# PCB_Project_Board_3.net
KiCad netlist of a schematic drawn in Altium Designer
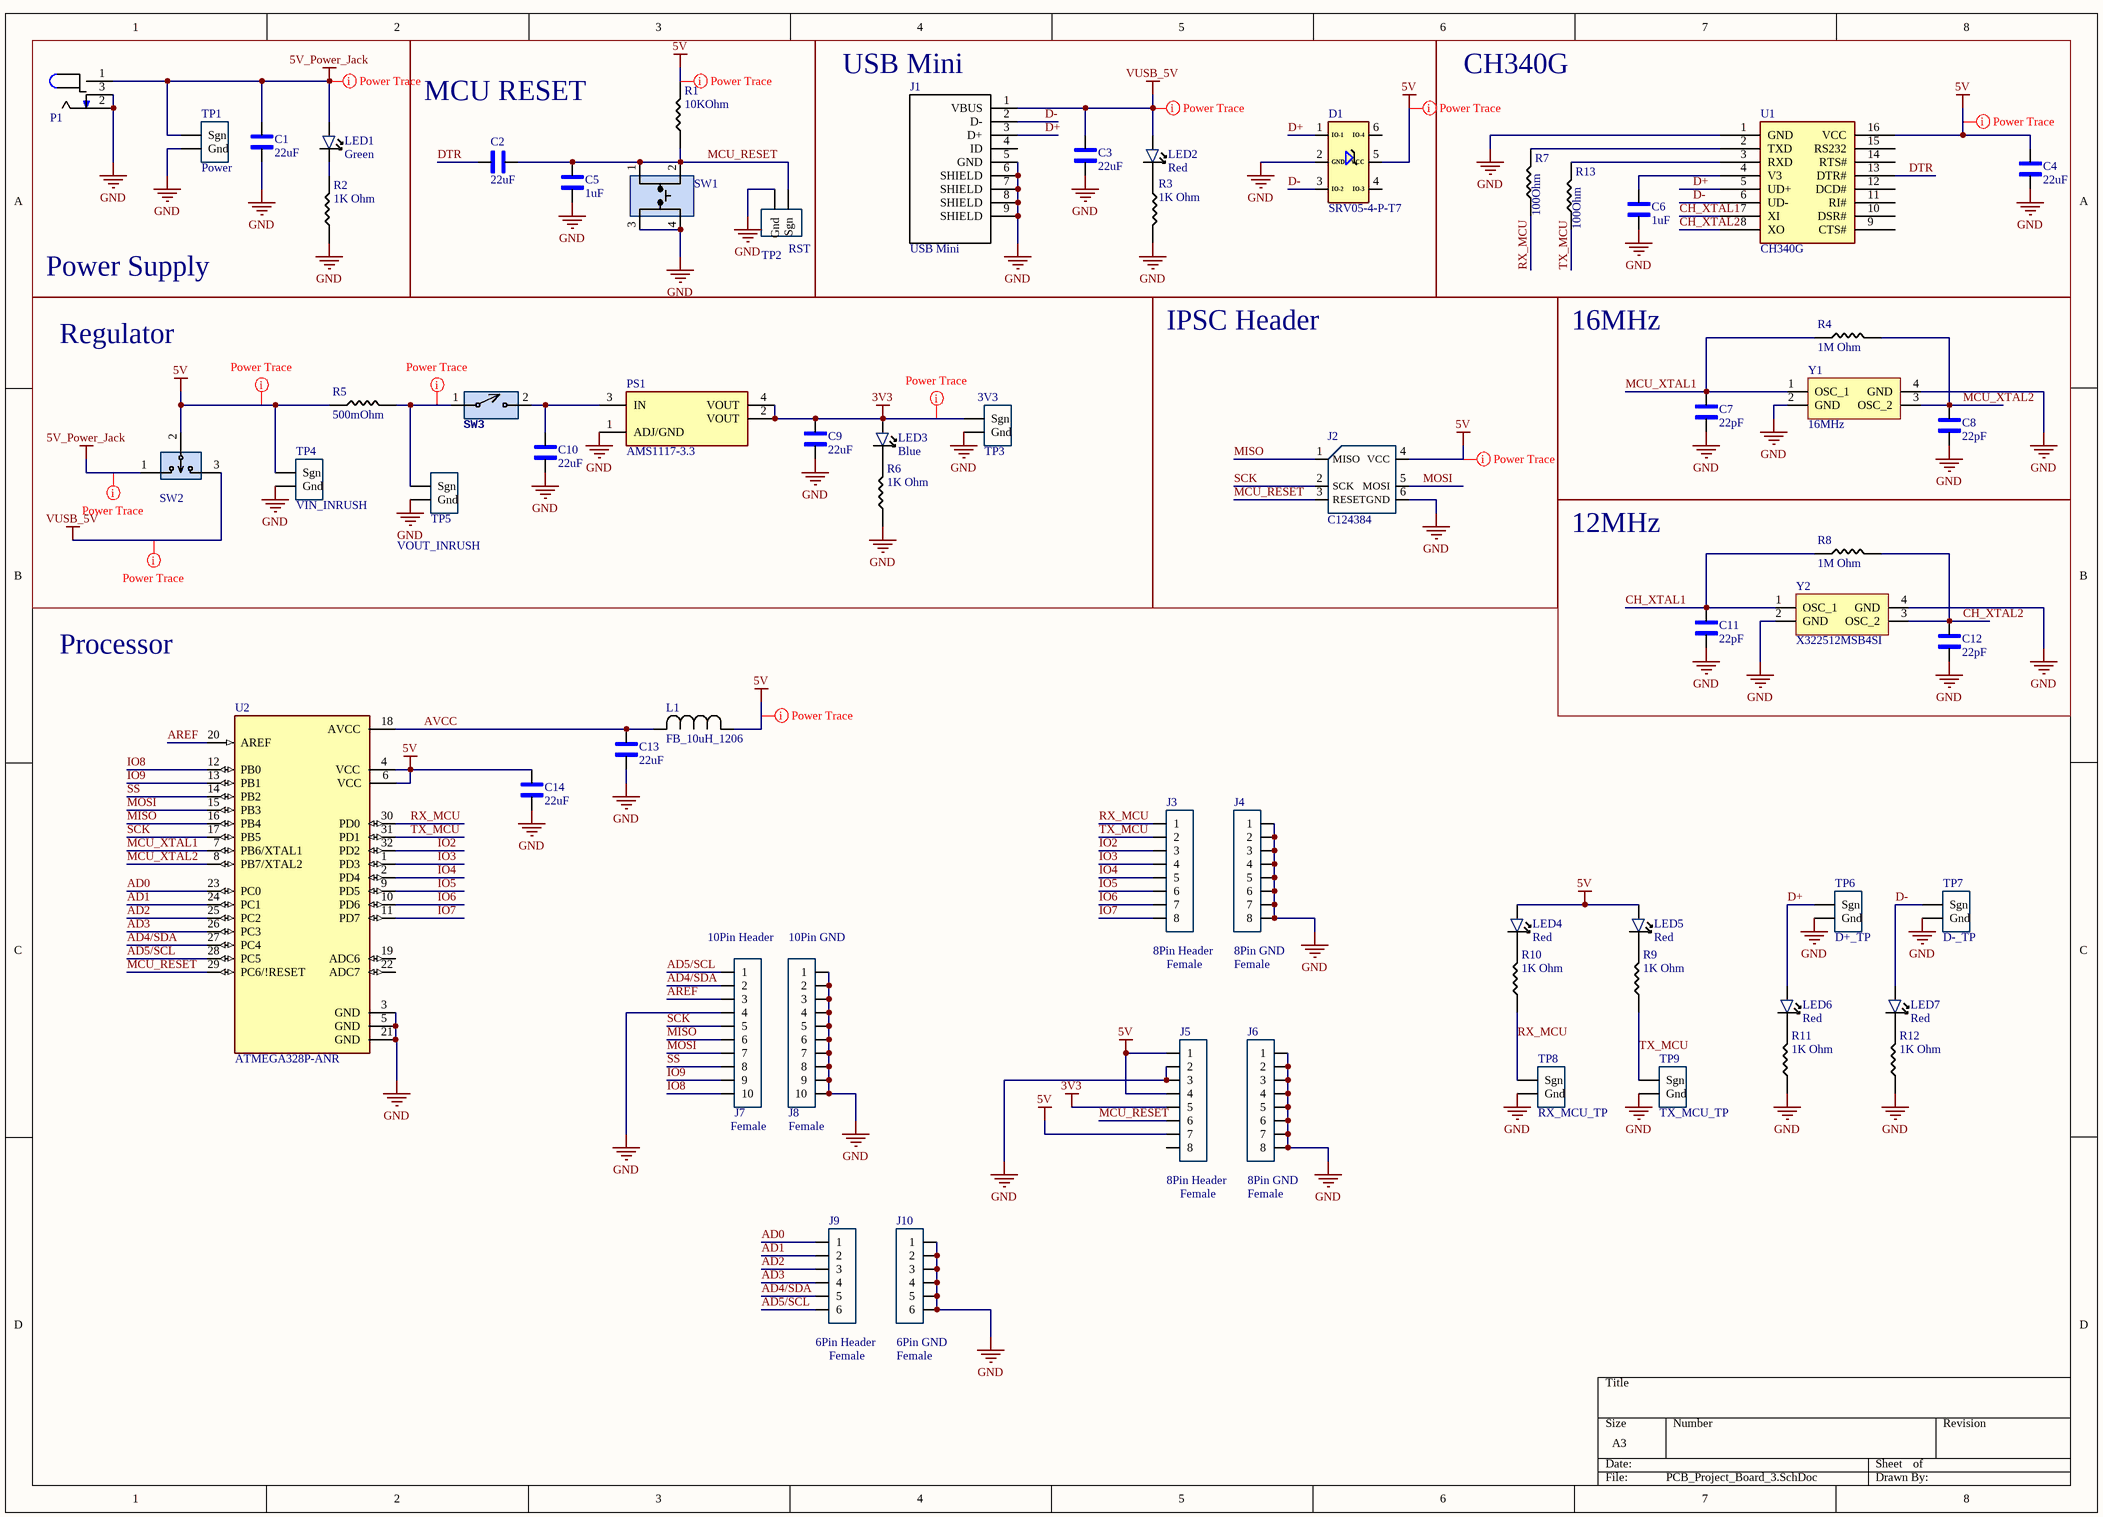
[diagram p0: PCB_Project_Board_3.SchDoc]

(export (version "E")
  (design (tool "Eeschema 10.0.6"))
  (components
    (comp (ref "C1")
      (value "22uF")
      (footprint "1206_Passive_Capacitor")
      (description "22uF ±10% 25V X5R 1206 Multilayer Ceramic Capacitors MLCC - SMD/SMT RoHS")
      (fields (field (name "MFR PART #") "CL31A226KAHNNNE") (field (name "LCSC PART#") "C12891"))
      (libsource (lib "ECEN5730Lib_2023_01_DS") (part "C_22uF_1206"))
    )
    (comp (ref "C2")
      (value "22uF")
      (footprint "1206_Passive_Capacitor")
      (description "22uF ±10% 25V X5R 1206 Multilayer Ceramic Capacitors MLCC - SMD/SMT RoHS")
      (fields (field (name "MFR PART #") "CL31A226KAHNNNE") (field (name "LCSC PART#") "C12891"))
      (libsource (lib "ECEN5730Lib_2023_01_DS") (part "C_22uF_1206"))
    )
    (comp (ref "C3")
      (value "22uF")
      (footprint "1206_Passive_Capacitor")
      (description "22uF ±10% 25V X5R 1206 Multilayer Ceramic Capacitors MLCC - SMD/SMT RoHS")
      (fields (field (name "MFR PART #") "CL31A226KAHNNNE") (field (name "LCSC PART#") "C12891"))
      (libsource (lib "ECEN5730Lib_2023_01_DS") (part "C_22uF_1206"))
    )
    (comp (ref "C4")
      (value "22uF")
      (footprint "1206_Passive_Capacitor")
      (description "22uF ±10% 25V X5R 1206 Multilayer Ceramic Capacitors MLCC - SMD/SMT RoHS")
      (fields (field (name "MFR PART #") "CL31A226KAHNNNE") (field (name "LCSC PART#") "C12891"))
      (libsource (lib "ECEN5730Lib_2023_01_DS") (part "C_22uF_1206"))
    )
    (comp (ref "C5")
      (value "1uF")
      (footprint "1206_Passive_Capacitor")
      (description "MULTILAYER CERAMIC CAPACITORS MLCC - SMD/SMT 1UF 50V 1206 ROHS")
      (fields (field (name "MFR PART #") "CL31B105KBHNNNE") (field (name "LCSC PART#") "C1848"))
      (libsource (lib "ECEN5730Lib_2023_01_DS") (part "C_1uF_1206"))
    )
    (comp (ref "C6")
      (value "1uF")
      (footprint "1206_Passive_Capacitor")
      (description "MULTILAYER CERAMIC CAPACITORS MLCC - SMD/SMT 1UF 50V 1206 ROHS")
      (fields (field (name "MFR PART #") "CL31B105KBHNNNE") (field (name "LCSC PART#") "C1848"))
      (libsource (lib "ECEN5730Lib_2023_01_DS") (part "C_1uF_1206"))
    )
    (comp (ref "C7")
      (value "22pF")
      (footprint "1206_Passive_Capacitor")
      (description "22pF ±5% 1kV C0G 1206 Multilayer Ceramic Capacitors MLCC - SMD/SMT RoHS")
      (fields (field (name "LCSC PART#") "C313096") (field (name "MFR PART #") "1206CG220J102NT"))
      (libsource (lib "ECEN5730Lib_2023_01_DS") (part "C_22pF_1206"))
    )
    (comp (ref "C8")
      (value "22pF")
      (footprint "1206_Passive_Capacitor")
      (description "22pF ±5% 1kV C0G 1206 Multilayer Ceramic Capacitors MLCC - SMD/SMT RoHS")
      (fields (field (name "LCSC PART#") "C313096") (field (name "MFR PART #") "1206CG220J102NT"))
      (libsource (lib "ECEN5730Lib_2023_01_DS") (part "C_22pF_1206"))
    )
    (comp (ref "C9")
      (value "22uF")
      (footprint "1206_Passive_Capacitor")
      (description "22uF ±10% 25V X5R 1206 Multilayer Ceramic Capacitors MLCC - SMD/SMT RoHS")
      (fields (field (name "MFR PART #") "CL31A226KAHNNNE") (field (name "LCSC PART#") "C12891"))
      (libsource (lib "ECEN5730Lib_2023_01_DS") (part "C_22uF_1206"))
    )
    (comp (ref "C10")
      (value "22uF")
      (footprint "1206_Passive_Capacitor")
      (description "22uF ±10% 25V X5R 1206 Multilayer Ceramic Capacitors MLCC - SMD/SMT RoHS")
      (fields (field (name "MFR PART #") "CL31A226KAHNNNE") (field (name "LCSC PART#") "C12891"))
      (libsource (lib "ECEN5730Lib_2023_01_DS") (part "C_22uF_1206"))
    )
    (comp (ref "C11")
      (value "22pF")
      (footprint "1206_Passive_Capacitor")
      (description "22pF ±5% 1kV C0G 1206 Multilayer Ceramic Capacitors MLCC - SMD/SMT RoHS")
      (fields (field (name "LCSC PART#") "C313096") (field (name "MFR PART #") "1206CG220J102NT"))
      (libsource (lib "ECEN5730Lib_2023_01_DS") (part "C_22pF_1206"))
    )
    (comp (ref "C12")
      (value "22pF")
      (footprint "1206_Passive_Capacitor")
      (description "22pF ±5% 1kV C0G 1206 Multilayer Ceramic Capacitors MLCC - SMD/SMT RoHS")
      (fields (field (name "LCSC PART#") "C313096") (field (name "MFR PART #") "1206CG220J102NT"))
      (libsource (lib "ECEN5730Lib_2023_01_DS") (part "C_22pF_1206"))
    )
    (comp (ref "C13")
      (value "22uF")
      (footprint "1206_Passive_Capacitor")
      (description "22uF ±10% 25V X5R 1206 Multilayer Ceramic Capacitors MLCC - SMD/SMT RoHS")
      (fields (field (name "MFR PART #") "CL31A226KAHNNNE") (field (name "LCSC PART#") "C12891"))
      (libsource (lib "ECEN5730Lib_2023_01_DS") (part "C_22uF_1206"))
    )
    (comp (ref "C14")
      (value "22uF")
      (footprint "1206_Passive_Capacitor")
      (description "22uF ±10% 25V X5R 1206 Multilayer Ceramic Capacitors MLCC - SMD/SMT RoHS")
      (fields (field (name "MFR PART #") "CL31A226KAHNNNE") (field (name "LCSC PART#") "C12891"))
      (libsource (lib "ECEN5730Lib_2023_01_DS") (part "C_22uF_1206"))
    )
    (comp (ref "D1")
      (value "SRV05-4-P-T7")
      (footprint "TVS")
      (description "TVS SOT-23-6 ROHS")
      (fields (field (name "LCSC PART#") "C85364"))
      (libsource (lib "ECEN5730Lib_2023_01_DS") (part "D_TVS_Diode"))
    )
    (comp (ref "J1")
      (value "USB Mini")
      (footprint "USB_MINI_B")
      (description "Through Hole USB Connectors RoHS")
      (fields (field (name "LCSC PART#") "C46398") (field (name "MFR PART #") "920-462A2021D10102"))
      (libsource (lib "ECEN5730Lib_2023_01_DS") (part "J_USB_B_Mini"))
    )
    (comp (ref "J2")
      (value "NRPN032PAEN-RC")
      (footprint "ICSP")
      (description "Connector Header Through Hole 6 position 0.079\" (2.00mm)")
      (fields (field (name "LCSC PART#") "C124384"))
      (libsource (lib "ECEN5730Lib_2023_01_DS") (part "J_ICSP"))
    )
    (comp (ref "J3")
      (value "8Pin Header")
      (footprint "8_PIN_100MIL - Female")
      (description "8 Position Header Connector 0.100\" (2.54mm) Through Hole Tin")
      (fields
        (field (name "MFR PART #") "PPTC081LFBN-RC")
        (field (name "LCSC PART#") "C27438")
        (field (name "ALTIUM_VALUE") "Female")
      )
      (libsource (lib "ECEN5730Lib_2023_01_DS") (part "JF_8_PIN_FEMALE"))
    )
    (comp (ref "J4")
      (value "8Pin GND")
      (footprint "8_PIN_100MIL - Female")
      (description "8 Position Header Connector 0.100\" (2.54mm) Through Hole Tin")
      (fields
        (field (name "MFR PART #") "PPTC081LFBN-RC")
        (field (name "LCSC PART#") "C27438")
        (field (name "ALTIUM_VALUE") "Female")
      )
      (libsource (lib "") (part "JF_8_PIN_FEMALE_1"))
    )
    (comp (ref "J5")
      (value "8Pin Header")
      (footprint "8_PIN_100MIL - Female")
      (description "8 Position Header Connector 0.100\" (2.54mm) Through Hole Tin")
      (fields
        (field (name "MFR PART #") "PPTC081LFBN-RC")
        (field (name "LCSC PART#") "C27438")
        (field (name "ALTIUM_VALUE") "Female")
      )
      (libsource (lib "ECEN5730Lib_2023_01_DS") (part "JF_8_PIN_FEMALE"))
    )
    (comp (ref "J6")
      (value "8Pin GND")
      (footprint "8_PIN_100MIL - Female")
      (description "8 Position Header Connector 0.100\" (2.54mm) Through Hole Tin")
      (fields
        (field (name "MFR PART #") "PPTC081LFBN-RC")
        (field (name "LCSC PART#") "C27438")
        (field (name "ALTIUM_VALUE") "Female")
      )
      (libsource (lib "") (part "JF_8_PIN_FEMALE_1"))
    )
    (comp (ref "J7")
      (value "10Pin Header")
      (footprint "10_PIN_100MIL - Female")
      (description "10 Position Header Connector 0.100\" (2.54mm) Through Hole Tin")
      (fields
        (field (name "MFR PART #") "PPTC101LFBN-RC")
        (field (name "LCSC PART#") "C225507")
        (field (name "ALTIUM_VALUE") "Female")
      )
      (libsource (lib "") (part "JF_10_PIN_FEMALE__1"))
    )
    (comp (ref "J8")
      (value "10Pin GND")
      (footprint "10_PIN_100MIL - Female")
      (description "10 Position Header Connector 0.100\" (2.54mm) Through Hole Tin")
      (fields
        (field (name "MFR PART #") "PPTC101LFBN-RC")
        (field (name "LCSC PART#") "C225507")
        (field (name "ALTIUM_VALUE") "Female")
      )
      (libsource (lib "ECEN5730Lib_2023_01_DS") (part "JF_10_PIN_FEMALE_"))
    )
    (comp (ref "J9")
      (value "6Pin Header")
      (footprint "6_PIN_100MIL -Female")
      (description "6 Position Header Connector 0.100\" (2.54mm) Through Hole Tin")
      (fields
        (field (name "MFR PART #") "PPTC061LFBN-RC")
        (field (name "LCSC PART#") "C40877")
        (field (name "ALTIUM_VALUE") "Female")
      )
      (libsource (lib "ECEN5730Lib_2023_01_DS") (part "JF_6_PIN_FEMALE"))
    )
    (comp (ref "J10")
      (value "6Pin GND")
      (footprint "6_PIN_100MIL -Female")
      (description "6 Position Header Connector 0.100\" (2.54mm) Through Hole Tin")
      (fields
        (field (name "MFR PART #") "PPTC061LFBN-RC")
        (field (name "LCSC PART#") "C40877")
        (field (name "ALTIUM_VALUE") "Female")
      )
      (libsource (lib "") (part "JF_6_PIN_FEMALE_1"))
    )
    (comp (ref "L1")
      (value "FB_10uH_1206")
      (footprint "AIML-1206_ABR-M")
      (description "25mA 10uH ±10% 800mΩ 1206  Inductors (SMD) ROHS")
      (fields (field (name "MFR PART #") "CMI321609X100KT") (field (name "LCSC PART#") "C1051"))
      (libsource (lib "ECEN5730Lib_2023_01_DS") (part "FB_10uH_1206"))
    )
    (comp (ref "LED1")
      (value "Green")
      (footprint "LED_1206")
      (description "Green 513~528nm 1206 Light Emitting Diodes (LED) RoHS")
      (fields (field (name "MFR PART #") "SZYY1206G") (field (name "LCSC PART#") "C434439"))
      (libsource (lib "ECEN5730Lib_2023_01_DS") (part "LED_GREEN_1206"))
    )
    (comp (ref "LED2")
      (value "Red")
      (footprint "LED_1206")
      (description "Red 621~631nm 1206 Light Emitting Diodes (LED) RoHS")
      (fields (field (name "MFR PART #") "15-21/R6C-FQ1R1B/2T") (field (name "LCSC PART#") "C93133"))
      (libsource (lib "ECEN5730Lib_2023_01_DS") (part "LED_RED_1206"))
    )
    (comp (ref "LED3")
      (value "Blue")
      (footprint "LED_1206")
      (description "blue 1206  Light Emitting Diodes (LED) ROHS")
      (fields (field (name "MFR PART #") "NCD1206B1") (field (name "LCSC PART#") "C130717"))
      (libsource (lib "ECEN5730Lib_2023_01_DS") (part "LED_BLUE_1206"))
    )
    (comp (ref "LED4")
      (value "Red")
      (footprint "LED_1206")
      (description "Red 621~631nm 1206 Light Emitting Diodes (LED) RoHS")
      (fields (field (name "MFR PART #") "15-21/R6C-FQ1R1B/2T") (field (name "LCSC PART#") "C93133"))
      (libsource (lib "ECEN5730Lib_2023_01_DS") (part "LED_RED_1206"))
    )
    (comp (ref "LED5")
      (value "Red")
      (footprint "LED_1206")
      (description "Red 621~631nm 1206 Light Emitting Diodes (LED) RoHS")
      (fields (field (name "MFR PART #") "15-21/R6C-FQ1R1B/2T") (field (name "LCSC PART#") "C93133"))
      (libsource (lib "ECEN5730Lib_2023_01_DS") (part "LED_RED_1206"))
    )
    (comp (ref "LED6")
      (value "Red")
      (footprint "LED_1206")
      (description "Red 621~631nm 1206 Light Emitting Diodes (LED) RoHS")
      (fields (field (name "MFR PART #") "15-21/R6C-FQ1R1B/2T") (field (name "LCSC PART#") "C93133"))
      (libsource (lib "ECEN5730Lib_2023_01_DS") (part "LED_RED_1206"))
    )
    (comp (ref "LED7")
      (value "Red")
      (footprint "LED_1206")
      (description "Red 621~631nm 1206 Light Emitting Diodes (LED) RoHS")
      (fields (field (name "MFR PART #") "15-21/R6C-FQ1R1B/2T") (field (name "LCSC PART#") "C93133"))
      (libsource (lib "ECEN5730Lib_2023_01_DS") (part "LED_RED_1206"))
    )
    (comp (ref "P1")
      (value "Power Jack")
      (footprint "Power_Jack")
      (description "Power Barrel Connector Jack 2.10mm ID (0.083\"), 5.50mm OD (0.217\") Through Hole, Right Angle")
      (fields (field (name "MFR PART #") "PJ-102A") (field (name "LCSC PART#") "C136744"))
      (libsource (lib "ECEN5730Lib_2023_01_DS") (part "P_Power Jack"))
    )
    (comp (ref "PS1")
      (value "AMS1117-3.3")
      (footprint "LDO")
      (description "LOW DROPOUT REGULATORS(LDO) POSITIVE FIXED 1.3V @ 800MA 15V 3.3V 1A SOT-223 ROHS")
      (fields (field (name "LCSC PART#") "C6186"))
      (libsource (lib "ECEN5730Lib_2023_01_DS") (part "PS_AMS_LDO_3v3"))
    )
    (comp (ref "R1")
      (value "10KOhm")
      (footprint "1206_Passive_Resitor")
      (description "10 kOhms ±5% 0.25W, 1/4W Chip Resistor 1206 (3216 Metric) Automotive AEC-Q200 Thick Film")
      (fields (field (name "MFR PART #") "RMCF1206FT10K0") (field (name "LCSC PART#") "C17902"))
      (libsource (lib "ECEN5730Lib_2023_01_DS") (part "R_10KOhm_1206"))
    )
    (comp (ref "R2")
      (value "1K Ohm")
      (footprint "1206_Passive_Resitor")
      (description "CHIP RESISTOR - SURFACE MOUNT 1KOHMS ±1% 1/4W 1206 ROHS")
      (fields (field (name "MFR PART #") "RNCP1206FTD1K00CT") (field (name "LCSC PART#") "C4410"))
      (libsource (lib "ECEN5730Lib_2023_01_DS") (part "R_1K_1206"))
    )
    (comp (ref "R3")
      (value "1K Ohm")
      (footprint "1206_Passive_Resitor")
      (description "CHIP RESISTOR - SURFACE MOUNT 1KOHMS ±1% 1/4W 1206 ROHS")
      (fields (field (name "MFR PART #") "RNCP1206FTD1K00CT") (field (name "LCSC PART#") "C4410"))
      (libsource (lib "ECEN5730Lib_2023_01_DS") (part "R_1K_1206"))
    )
    (comp (ref "R4")
      (value "1M Ohm")
      (footprint "1206_Passive_Resitor")
      (description "CHIP RESISTOR - SURFACE MOUNT 1MOHMS ±1% 1/4W 1206 ROHS")
      (fields (field (name "MFR PART #") "RMCF1206JT1M00") (field (name "LCSC PART#") "C17927"))
      (libsource (lib "ECEN5730Lib_2023_01_DS") (part "R_1M_1206"))
    )
    (comp (ref "R5")
      (value "500mOhm")
      (footprint "1206_Passive_Resitor")
      (description "Resistors/Shunt 250mW 500mΩ ±800ppm/℃ ±5% 1206  Current Sense  Resistors ROHS")
      (fields (field (name "MFR PART #") "1206W4J050KT5E") (field (name "LCSC PART#") "C247433"))
      (libsource (lib "ECEN5730Lib_2023_01_DS") (part "R_500mOhm_1206"))
    )
    (comp (ref "R6")
      (value "1K Ohm")
      (footprint "1206_Passive_Resitor")
      (description "CHIP RESISTOR - SURFACE MOUNT 1KOHMS ±1% 1/4W 1206 ROHS")
      (fields (field (name "MFR PART #") "RNCP1206FTD1K00CT") (field (name "LCSC PART#") "C4410"))
      (libsource (lib "ECEN5730Lib_2023_01_DS") (part "R_1K_1206"))
    )
    (comp (ref "R7")
      (value "100Ohm")
      (footprint "1206_Passive_Resitor")
      (description "100Ω ±1% 0.25W ±100ppm/℃ 1206 Chip Resistor - Surface Mount RoHS")
      (fields (field (name "LCSC PART#") "C17901") (field (name "MFR PART #") "1206W4F1000T5E"))
      (libsource (lib "ECEN5730Lib_2023_01_DS") (part "R_100Ohm_1206"))
    )
    (comp (ref "R8")
      (value "1M Ohm")
      (footprint "1206_Passive_Resitor")
      (description "CHIP RESISTOR - SURFACE MOUNT 1MOHMS ±1% 1/4W 1206 ROHS")
      (fields (field (name "MFR PART #") "RMCF1206JT1M00") (field (name "LCSC PART#") "C17927"))
      (libsource (lib "ECEN5730Lib_2023_01_DS") (part "R_1M_1206"))
    )
    (comp (ref "R9")
      (value "1K Ohm")
      (footprint "1206_Passive_Resitor")
      (description "CHIP RESISTOR - SURFACE MOUNT 1KOHMS ±1% 1/4W 1206 ROHS")
      (fields (field (name "MFR PART #") "RNCP1206FTD1K00CT") (field (name "LCSC PART#") "C4410"))
      (libsource (lib "ECEN5730Lib_2023_01_DS") (part "R_1K_1206"))
    )
    (comp (ref "R10")
      (value "1K Ohm")
      (footprint "1206_Passive_Resitor")
      (description "CHIP RESISTOR - SURFACE MOUNT 1KOHMS ±1% 1/4W 1206 ROHS")
      (fields (field (name "MFR PART #") "RNCP1206FTD1K00CT") (field (name "LCSC PART#") "C4410"))
      (libsource (lib "ECEN5730Lib_2023_01_DS") (part "R_1K_1206"))
    )
    (comp (ref "R11")
      (value "1K Ohm")
      (footprint "1206_Passive_Resitor")
      (description "CHIP RESISTOR - SURFACE MOUNT 1KOHMS ±1% 1/4W 1206 ROHS")
      (fields (field (name "MFR PART #") "RNCP1206FTD1K00CT") (field (name "LCSC PART#") "C4410"))
      (libsource (lib "ECEN5730Lib_2023_01_DS") (part "R_1K_1206"))
    )
    (comp (ref "R12")
      (value "1K Ohm")
      (footprint "1206_Passive_Resitor")
      (description "CHIP RESISTOR - SURFACE MOUNT 1KOHMS ±1% 1/4W 1206 ROHS")
      (fields (field (name "MFR PART #") "RNCP1206FTD1K00CT") (field (name "LCSC PART#") "C4410"))
      (libsource (lib "ECEN5730Lib_2023_01_DS") (part "R_1K_1206"))
    )
    (comp (ref "R13")
      (value "100Ohm")
      (footprint "1206_Passive_Resitor")
      (description "100Ω ±1% 0.25W ±100ppm/℃ 1206 Chip Resistor - Surface Mount RoHS")
      (fields (field (name "LCSC PART#") "C17901") (field (name "MFR PART #") "1206W4F1000T5E"))
      (libsource (lib "ECEN5730Lib_2023_01_DS") (part "R_100Ohm_1206"))
    )
    (comp (ref "SW1")
      (value "TL3305AF160QG")
      (footprint "Switch_JLC")
      (description "Tactile Switch SPST-NO Top Actuated Surface Mount")
      (fields (field (name "MFR PART #") "KH-4.5X4.5X4.3H-STM") (field (name "LCSC PART#") "C2837550"))
      (libsource (lib "ECEN5730Lib_2023_01_DS") (part "SW_Push_Button_JLC"))
    )
    (comp (ref "SW2")
      (value "PREC003SAAN-RC")
      (footprint "3_PIN_100mil")
      (description "Connector Header Through Hole 3 position 0.100\" (2.54mm)")
      (fields (field (name "LCSC PART#") "C49257"))
      (libsource (lib "ECEN5730Lib_2023_01_DS") (part "SW_3Pin_100mil_Switch"))
    )
    (comp (ref "SW3")
      (value "SW_2Pin_100mil_Switch")
      (footprint "2Pin-Header-Conn")
      (description "2Pin Header")
      (fields (field (name "LCSC PART#") "C124375"))
      (libsource (lib "ECEN5730Lib_2023_01_DS") (part "SW_2Pin_100mil_Switch"))
    )
    (comp (ref "TP1")
      (value "Power")
      (footprint "TP10x_Probe")
      (description "Test Point 300 mil centers")
      (libsource (lib "ECEN5730Lib_2023_01_DS") (part "TP_10x_Probe"))
    )
    (comp (ref "TP2")
      (value "RST")
      (footprint "TP10x_Probe")
      (description "Test Point 300 mil centers")
      (libsource (lib "") (part "TP_10x_Probe_1"))
    )
    (comp (ref "TP3")
      (value "3V3")
      (footprint "TP10x_Probe")
      (description "Test Point 300 mil centers")
      (libsource (lib "ECEN5730Lib_2023_01_DS") (part "TP_10x_Probe"))
    )
    (comp (ref "TP4")
      (value "VIN_INRUSH")
      (footprint "TP10x_Probe")
      (description "Test Point 300 mil centers")
      (libsource (lib "ECEN5730Lib_2023_01_DS") (part "TP_10x_Probe"))
    )
    (comp (ref "TP5")
      (value "VOUT_INRUSH")
      (footprint "TP10x_Probe")
      (description "Test Point 300 mil centers")
      (libsource (lib "ECEN5730Lib_2023_01_DS") (part "TP_10x_Probe"))
    )
    (comp (ref "TP6")
      (value "D+_TP")
      (footprint "TP10x_Probe")
      (description "Test Point 300 mil centers")
      (libsource (lib "ECEN5730Lib_2023_01_DS") (part "TP_10x_Probe"))
    )
    (comp (ref "TP7")
      (value "D-_TP")
      (footprint "TP10x_Probe")
      (description "Test Point 300 mil centers")
      (libsource (lib "ECEN5730Lib_2023_01_DS") (part "TP_10x_Probe"))
    )
    (comp (ref "TP8")
      (value "RX_MCU_TP")
      (footprint "TP10x_Probe")
      (description "Test Point 300 mil centers")
      (libsource (lib "ECEN5730Lib_2023_01_DS") (part "TP_10x_Probe"))
    )
    (comp (ref "TP9")
      (value "TX_MCU_TP")
      (footprint "TP10x_Probe")
      (description "Test Point 300 mil centers")
      (libsource (lib "ECEN5730Lib_2023_01_DS") (part "TP_10x_Probe"))
    )
    (comp (ref "U1")
      (value "CH340G")
      (footprint "USB to serial")
      (description "Transceiver USB 2.0 2Mbps SOP-16_150mil USB ICs RoHS")
      (fields (field (name "LCSC PART#") "C14267"))
      (libsource (lib "ECEN5730Lib_2023_01_DS") (part "U_USBtoSerial"))
    )
    (comp (ref "U2")
      (value "ATMEGA328P-ANR")
      (footprint "ATMega328P")
      (description "AVR AVR® ATmega Microcontroller IC 8-Bit 20MHz 32KB (16K x 16) FLASH 32-TQFP (7x7)")
      (fields (field (name "MFR PART #") "ATMEGA328P-AU") (field (name "LCSC PART#") "C14877"))
      (libsource (lib "ECEN5730Lib_2023_01_DS") (part "U_ATMega328P"))
    )
    (comp (ref "Y1")
      (value "16MHz")
      (footprint "Crystal resonator")
      (description "±10ppm 16000000Hz -40℃~85℃ 贴片无源晶振 60Ω 9pF SMD3225-4P Crystals ROHS")
      (fields (field (name "LCSC PART#") "C13738") (field (name "MFR PART #") "X322516MLB4SI"))
      (libsource (lib "ECEN5730Lib_2023_01_DS") (part "X_16Mhz_Res"))
    )
    (comp (ref "Y2")
      (value "X322512MSB4SI")
      (footprint "Crystal resonator")
      (description "SMD Crystal Resonators 12MHz ±10ppm SMD-3225_4P RoHS")
      (fields (field (name "LCSC PART#") "C9002"))
      (libsource (lib "ECEN5730Lib_2023_01_DS") (part "X_12MHz_Res"))
    )
  )
  (nets
    (net (code "1") (name "/AD0") (class "Default")
      (node (ref "J9") (pin "1") (pinfunction "1_1") (pintype "passive"))
      (node (ref "U2") (pin "23") (pinfunction "PC0_23") (pintype "bidirectional"))
    )
    (net (code "2") (name "/AD1") (class "Default")
      (node (ref "J9") (pin "2") (pinfunction "2_2") (pintype "passive"))
      (node (ref "U2") (pin "24") (pinfunction "PC1_24") (pintype "bidirectional"))
    )
    (net (code "3") (name "/AD2") (class "Default")
      (node (ref "J9") (pin "3") (pinfunction "3_3") (pintype "passive"))
      (node (ref "U2") (pin "25") (pinfunction "PC2_25") (pintype "bidirectional"))
    )
    (net (code "4") (name "/AD3") (class "Default")
      (node (ref "J9") (pin "4") (pinfunction "4_4") (pintype "passive"))
      (node (ref "U2") (pin "26") (pinfunction "PC3_26") (pintype "bidirectional"))
    )
    (net (code "5") (name "/AD4{slash}SDA") (class "Default")
      (node (ref "J7") (pin "2") (pinfunction "2_2") (pintype "passive"))
      (node (ref "J9") (pin "5") (pinfunction "5_5") (pintype "passive"))
      (node (ref "U2") (pin "27") (pinfunction "PC4_27") (pintype "bidirectional"))
    )
    (net (code "6") (name "/AD5{slash}SCL") (class "Default")
      (node (ref "J7") (pin "1") (pinfunction "1_1") (pintype "passive"))
      (node (ref "J9") (pin "6") (pinfunction "6_6") (pintype "passive"))
      (node (ref "U2") (pin "28") (pinfunction "PC5_28") (pintype "bidirectional"))
    )
    (net (code "7") (name "/AREF") (class "Default")
      (node (ref "J7") (pin "3") (pinfunction "3_3") (pintype "passive"))
      (node (ref "U2") (pin "20") (pinfunction "AREF_20") (pintype "input"))
    )
    (net (code "8") (name "/AVCC") (class "Default")
      (node (ref "C13") (pin "2") (pinfunction "2_2") (pintype "passive"))
      (node (ref "L1") (pin "2") (pinfunction "2_2") (pintype "passive"))
      (node (ref "U2") (pin "18") (pinfunction "AVCC_18") (pintype "power_in"))
    )
    (net (code "9") (name "/CH_XTAL1") (class "Default")
      (node (ref "C11") (pin "2") (pinfunction "2_2") (pintype "passive"))
      (node (ref "R8") (pin "1") (pinfunction "1_1") (pintype "passive"))
      (node (ref "U1") (pin "7") (pinfunction "XI_7") (pintype "passive"))
      (node (ref "Y2") (pin "1") (pinfunction "OSC_1_1") (pintype "passive"))
    )
    (net (code "10") (name "/CH_XTAL2") (class "Default")
      (node (ref "C12") (pin "2") (pinfunction "2_2") (pintype "passive"))
      (node (ref "R8") (pin "2") (pinfunction "2_2") (pintype "passive"))
      (node (ref "U1") (pin "8") (pinfunction "XO_8") (pintype "passive"))
      (node (ref "Y2") (pin "3") (pinfunction "OSC_2_3") (pintype "passive"))
    )
    (net (code "11") (name "/D+") (class "Default")
      (node (ref "D1") (pin "1") (pinfunction "IO-1_1") (pintype "passive"))
      (node (ref "J1") (pin "3") (pinfunction "D+_3") (pintype "passive"))
      (node (ref "LED6") (pin "1") (pinfunction "1_1") (pintype "passive"))
      (node (ref "TP6") (pin "1") (pinfunction "Sgn_1") (pintype "passive"))
      (node (ref "U1") (pin "5") (pinfunction "UD+_5") (pintype "passive"))
    )
    (net (code "12") (name "/D-") (class "Default")
      (node (ref "D1") (pin "3") (pinfunction "IO-2_3") (pintype "passive"))
      (node (ref "J1") (pin "2") (pinfunction "D-_2") (pintype "passive"))
      (node (ref "LED7") (pin "1") (pinfunction "1_1") (pintype "passive"))
      (node (ref "TP7") (pin "1") (pinfunction "Sgn_1") (pintype "passive"))
      (node (ref "U1") (pin "6") (pinfunction "UD-_6") (pintype "passive"))
    )
    (net (code "13") (name "/DTR") (class "Default")
      (node (ref "C2") (pin "1") (pinfunction "1_1") (pintype "passive"))
      (node (ref "U1") (pin "13") (pinfunction "DTR#_13") (pintype "passive"))
    )
    (net (code "14") (name "/IO2") (class "Default")
      (node (ref "J3") (pin "3") (pinfunction "3_3") (pintype "passive"))
      (node (ref "U2") (pin "32") (pinfunction "PD2_32") (pintype "bidirectional"))
    )
    (net (code "15") (name "/IO3") (class "Default")
      (node (ref "J3") (pin "4") (pinfunction "4_4") (pintype "passive"))
      (node (ref "U2") (pin "1") (pinfunction "PD3_1") (pintype "bidirectional"))
    )
    (net (code "16") (name "/IO4") (class "Default")
      (node (ref "J3") (pin "5") (pinfunction "5_5") (pintype "passive"))
      (node (ref "U2") (pin "2") (pinfunction "PD4_2") (pintype "bidirectional"))
    )
    (net (code "17") (name "/IO5") (class "Default")
      (node (ref "J3") (pin "6") (pinfunction "6_6") (pintype "passive"))
      (node (ref "U2") (pin "9") (pinfunction "PD5_9") (pintype "bidirectional"))
    )
    (net (code "18") (name "/IO6") (class "Default")
      (node (ref "J3") (pin "7") (pinfunction "7_7") (pintype "passive"))
      (node (ref "U2") (pin "10") (pinfunction "PD6_10") (pintype "bidirectional"))
    )
    (net (code "19") (name "/IO7") (class "Default")
      (node (ref "J3") (pin "8") (pinfunction "8_8") (pintype "passive"))
      (node (ref "U2") (pin "11") (pinfunction "PD7_11") (pintype "bidirectional"))
    )
    (net (code "20") (name "/IO8") (class "Default")
      (node (ref "J7") (pin "10") (pinfunction "10_10") (pintype "passive"))
      (node (ref "U2") (pin "12") (pinfunction "PB0_12") (pintype "bidirectional"))
    )
    (net (code "21") (name "/IO9") (class "Default")
      (node (ref "J7") (pin "9") (pinfunction "9_9") (pintype "passive"))
      (node (ref "U2") (pin "13") (pinfunction "PB1_13") (pintype "bidirectional"))
    )
    (net (code "22") (name "/MCU_RESET") (class "Default")
      (node (ref "C2") (pin "2") (pinfunction "2_2") (pintype "passive"))
      (node (ref "C5") (pin "2") (pinfunction "2_2") (pintype "passive"))
      (node (ref "J2") (pin "3") (pinfunction "RESET_3") (pintype "passive"))
      (node (ref "J5") (pin "6") (pinfunction "6_6") (pintype "passive"))
      (node (ref "R1") (pin "1") (pinfunction "1_1") (pintype "passive"))
      (node (ref "SW1") (pin "1") (pinfunction "1_1") (pintype "passive"))
      (node (ref "SW1") (pin "2") (pinfunction "2_2") (pintype "passive"))
      (node (ref "TP2") (pin "1") (pinfunction "Sgn_1") (pintype "passive"))
      (node (ref "U2") (pin "29") (pinfunction "PC6/!RESET_29") (pintype "bidirectional"))
    )
    (net (code "23") (name "/MCU_XTAL1") (class "Default")
      (node (ref "C7") (pin "2") (pinfunction "2_2") (pintype "passive"))
      (node (ref "R4") (pin "1") (pinfunction "1_1") (pintype "passive"))
      (node (ref "U2") (pin "7") (pinfunction "PB6/XTAL1_7") (pintype "bidirectional"))
      (node (ref "Y1") (pin "1") (pinfunction "OSC_1_1") (pintype "passive"))
    )
    (net (code "24") (name "/MCU_XTAL2") (class "Default")
      (node (ref "C8") (pin "2") (pinfunction "2_2") (pintype "passive"))
      (node (ref "R4") (pin "2") (pinfunction "2_2") (pintype "passive"))
      (node (ref "U2") (pin "8") (pinfunction "PB7/XTAL2_8") (pintype "bidirectional"))
      (node (ref "Y1") (pin "3") (pinfunction "OSC_2_3") (pintype "passive"))
    )
    (net (code "25") (name "/MISO") (class "Default")
      (node (ref "J2") (pin "1") (pinfunction "MISO_1") (pintype "passive"))
      (node (ref "J7") (pin "6") (pinfunction "6_6") (pintype "passive"))
      (node (ref "U2") (pin "16") (pinfunction "PB4_16") (pintype "bidirectional"))
    )
    (net (code "26") (name "/MOSI") (class "Default")
      (node (ref "J2") (pin "5") (pinfunction "MOSI_5") (pintype "passive"))
      (node (ref "J7") (pin "7") (pinfunction "7_7") (pintype "passive"))
      (node (ref "U2") (pin "15") (pinfunction "PB3_15") (pintype "bidirectional"))
    )
    (net (code "27") (name "/RX_MCU") (class "Default")
      (node (ref "J3") (pin "1") (pinfunction "1_1") (pintype "passive"))
      (node (ref "R10") (pin "1") (pinfunction "1_1") (pintype "passive"))
      (node (ref "R7") (pin "1") (pinfunction "1_1") (pintype "passive"))
      (node (ref "TP8") (pin "1") (pinfunction "Sgn_1") (pintype "passive"))
      (node (ref "U2") (pin "30") (pinfunction "PD0_30") (pintype "bidirectional"))
    )
    (net (code "28") (name "/SCK") (class "Default")
      (node (ref "J2") (pin "2") (pinfunction "SCK_2") (pintype "passive"))
      (node (ref "J7") (pin "5") (pinfunction "5_5") (pintype "passive"))
      (node (ref "U2") (pin "17") (pinfunction "PB5_17") (pintype "bidirectional"))
    )
    (net (code "29") (name "/SS") (class "Default")
      (node (ref "J7") (pin "8") (pinfunction "8_8") (pintype "passive"))
      (node (ref "U2") (pin "14") (pinfunction "PB2_14") (pintype "bidirectional"))
    )
    (net (code "30") (name "/TX_MCU") (class "Default")
      (node (ref "J3") (pin "2") (pinfunction "2_2") (pintype "passive"))
      (node (ref "R13") (pin "1") (pinfunction "1_1") (pintype "passive"))
      (node (ref "R9") (pin "1") (pinfunction "1_1") (pintype "passive"))
      (node (ref "TP9") (pin "1") (pinfunction "Sgn_1") (pintype "passive"))
      (node (ref "U2") (pin "31") (pinfunction "PD1_31") (pintype "bidirectional"))
    )
    (net (code "31") (name "3V3") (class "Default")
      (node (ref "C9") (pin "2") (pinfunction "2_2") (pintype "passive"))
      (node (ref "J5") (pin "5") (pinfunction "5_5") (pintype "passive"))
      (node (ref "LED3") (pin "1") (pinfunction "1_1") (pintype "passive"))
      (node (ref "PS1") (pin "2") (pinfunction "VOUT_2") (pintype "power_in"))
      (node (ref "PS1") (pin "4") (pinfunction "VOUT_4") (pintype "power_in"))
      (node (ref "TP3") (pin "1") (pinfunction "Sgn_1") (pintype "passive"))
    )
    (net (code "32") (name "5V") (class "Default")
      (node (ref "C14") (pin "2") (pinfunction "2_2") (pintype "passive"))
      (node (ref "C4") (pin "2") (pinfunction "2_2") (pintype "passive"))
      (node (ref "D1") (pin "5") (pinfunction "VCC_5") (pintype "passive"))
      (node (ref "J2") (pin "4") (pinfunction "VCC_4") (pintype "passive"))
      (node (ref "J5") (pin "1") (pinfunction "1_1") (pintype "passive"))
      (node (ref "J5") (pin "4") (pinfunction "4_4") (pintype "passive"))
      (node (ref "J5") (pin "7") (pinfunction "7_7") (pintype "passive"))
      (node (ref "L1") (pin "1") (pinfunction "1_1") (pintype "passive"))
      (node (ref "LED4") (pin "1") (pinfunction "1_1") (pintype "passive"))
      (node (ref "LED5") (pin "1") (pinfunction "1_1") (pintype "passive"))
      (node (ref "R1") (pin "2") (pinfunction "2_2") (pintype "passive"))
      (node (ref "R5") (pin "1") (pinfunction "1_1") (pintype "passive"))
      (node (ref "SW2") (pin "2") (pinfunction "2_2") (pintype "passive"))
      (node (ref "TP4") (pin "1") (pinfunction "Sgn_1") (pintype "passive"))
      (node (ref "U1") (pin "16") (pinfunction "VCC_16") (pintype "passive"))
      (node (ref "U2") (pin "4") (pinfunction "VCC_4") (pintype "power_in"))
      (node (ref "U2") (pin "6") (pinfunction "VCC_6") (pintype "power_in"))
    )
    (net (code "33") (name "5V_Power_Jack") (class "Default")
      (node (ref "C1") (pin "2") (pinfunction "2_2") (pintype "passive"))
      (node (ref "LED1") (pin "1") (pinfunction "1_1") (pintype "passive"))
      (node (ref "P1") (pin "1") (pinfunction "1_1") (pintype "power_in"))
      (node (ref "SW2") (pin "1") (pinfunction "1_1") (pintype "passive"))
      (node (ref "TP1") (pin "1") (pinfunction "Sgn_1") (pintype "passive"))
    )
    (net (code "34") (name "GND") (class "Default")
      (node (ref "C1") (pin "1") (pinfunction "1_1") (pintype "passive"))
      (node (ref "C10") (pin "1") (pinfunction "1_1") (pintype "passive"))
      (node (ref "C11") (pin "1") (pinfunction "1_1") (pintype "passive"))
      (node (ref "C12") (pin "1") (pinfunction "1_1") (pintype "passive"))
      (node (ref "C13") (pin "1") (pinfunction "1_1") (pintype "passive"))
      (node (ref "C14") (pin "1") (pinfunction "1_1") (pintype "passive"))
      (node (ref "C3") (pin "1") (pinfunction "1_1") (pintype "passive"))
      (node (ref "C4") (pin "1") (pinfunction "1_1") (pintype "passive"))
      (node (ref "C5") (pin "1") (pinfunction "1_1") (pintype "passive"))
      (node (ref "C6") (pin "1") (pinfunction "1_1") (pintype "passive"))
      (node (ref "C7") (pin "1") (pinfunction "1_1") (pintype "passive"))
      (node (ref "C8") (pin "1") (pinfunction "1_1") (pintype "passive"))
      (node (ref "C9") (pin "1") (pinfunction "1_1") (pintype "passive"))
      (node (ref "D1") (pin "2") (pinfunction "GND_2") (pintype "passive"))
      (node (ref "J1") (pin "5") (pinfunction "GND_5") (pintype "passive"))
      (node (ref "J1") (pin "6") (pinfunction "SHIELD_6") (pintype "passive"))
      (node (ref "J1") (pin "7") (pinfunction "SHIELD_7") (pintype "passive"))
      (node (ref "J1") (pin "8") (pinfunction "SHIELD_8") (pintype "passive"))
      (node (ref "J1") (pin "9") (pinfunction "SHIELD_9") (pintype "passive"))
      (node (ref "J10") (pin "1") (pinfunction "1_1") (pintype "passive"))
      (node (ref "J10") (pin "2") (pinfunction "2_2") (pintype "passive"))
      (node (ref "J10") (pin "3") (pinfunction "3_3") (pintype "passive"))
      (node (ref "J10") (pin "4") (pinfunction "4_4") (pintype "passive"))
      (node (ref "J10") (pin "5") (pinfunction "5_5") (pintype "passive"))
      (node (ref "J10") (pin "6") (pinfunction "6_6") (pintype "passive"))
      (node (ref "J2") (pin "6") (pinfunction "GND_6") (pintype "passive"))
      (node (ref "J4") (pin "1") (pinfunction "1_1") (pintype "passive"))
      (node (ref "J4") (pin "2") (pinfunction "2_2") (pintype "passive"))
      (node (ref "J4") (pin "3") (pinfunction "3_3") (pintype "passive"))
      (node (ref "J4") (pin "4") (pinfunction "4_4") (pintype "passive"))
      (node (ref "J4") (pin "5") (pinfunction "5_5") (pintype "passive"))
      (node (ref "J4") (pin "6") (pinfunction "6_6") (pintype "passive"))
      (node (ref "J4") (pin "7") (pinfunction "7_7") (pintype "passive"))
      (node (ref "J4") (pin "8") (pinfunction "8_8") (pintype "passive"))
      (node (ref "J5") (pin "2") (pinfunction "2_2") (pintype "passive"))
      (node (ref "J5") (pin "3") (pinfunction "3_3") (pintype "passive"))
      (node (ref "J6") (pin "1") (pinfunction "1_1") (pintype "passive"))
      (node (ref "J6") (pin "2") (pinfunction "2_2") (pintype "passive"))
      (node (ref "J6") (pin "3") (pinfunction "3_3") (pintype "passive"))
      (node (ref "J6") (pin "4") (pinfunction "4_4") (pintype "passive"))
      (node (ref "J6") (pin "5") (pinfunction "5_5") (pintype "passive"))
      (node (ref "J6") (pin "6") (pinfunction "6_6") (pintype "passive"))
      (node (ref "J6") (pin "7") (pinfunction "7_7") (pintype "passive"))
      (node (ref "J6") (pin "8") (pinfunction "8_8") (pintype "passive"))
      (node (ref "J7") (pin "4") (pinfunction "4_4") (pintype "passive"))
      (node (ref "J8") (pin "1") (pinfunction "1_1") (pintype "passive"))
      (node (ref "J8") (pin "10") (pinfunction "10_10") (pintype "passive"))
      (node (ref "J8") (pin "2") (pinfunction "2_2") (pintype "passive"))
      (node (ref "J8") (pin "3") (pinfunction "3_3") (pintype "passive"))
      (node (ref "J8") (pin "4") (pinfunction "4_4") (pintype "passive"))
      (node (ref "J8") (pin "5") (pinfunction "5_5") (pintype "passive"))
      (node (ref "J8") (pin "6") (pinfunction "6_6") (pintype "passive"))
      (node (ref "J8") (pin "7") (pinfunction "7_7") (pintype "passive"))
      (node (ref "J8") (pin "8") (pinfunction "8_8") (pintype "passive"))
      (node (ref "J8") (pin "9") (pinfunction "9_9") (pintype "passive"))
      (node (ref "P1") (pin "2") (pinfunction "2_2") (pintype "power_in"))
      (node (ref "P1") (pin "3") (pinfunction "3_3") (pintype "power_in"))
      (node (ref "PS1") (pin "1") (pinfunction "ADJ/GND_1") (pintype "passive"))
      (node (ref "R11") (pin "1") (pinfunction "1_1") (pintype "passive"))
      (node (ref "R12") (pin "1") (pinfunction "1_1") (pintype "passive"))
      (node (ref "R2") (pin "1") (pinfunction "1_1") (pintype "passive"))
      (node (ref "R3") (pin "2") (pinfunction "2_2") (pintype "passive"))
      (node (ref "R6") (pin "1") (pinfunction "1_1") (pintype "passive"))
      (node (ref "SW1") (pin "3") (pinfunction "3_3") (pintype "passive"))
      (node (ref "SW1") (pin "4") (pinfunction "4_4") (pintype "passive"))
      (node (ref "TP1") (pin "2") (pinfunction "Gnd_2") (pintype "passive"))
      (node (ref "TP2") (pin "2") (pinfunction "Gnd_2") (pintype "passive"))
      (node (ref "TP3") (pin "2") (pinfunction "Gnd_2") (pintype "passive"))
      (node (ref "TP4") (pin "2") (pinfunction "Gnd_2") (pintype "passive"))
      (node (ref "TP5") (pin "2") (pinfunction "Gnd_2") (pintype "passive"))
      (node (ref "TP6") (pin "2") (pinfunction "Gnd_2") (pintype "passive"))
      (node (ref "TP7") (pin "2") (pinfunction "Gnd_2") (pintype "passive"))
      (node (ref "TP8") (pin "2") (pinfunction "Gnd_2") (pintype "passive"))
      (node (ref "TP9") (pin "2") (pinfunction "Gnd_2") (pintype "passive"))
      (node (ref "U1") (pin "1") (pinfunction "GND_1") (pintype "passive"))
      (node (ref "U2") (pin "21") (pinfunction "GND_21") (pintype "power_in"))
      (node (ref "U2") (pin "3") (pinfunction "GND_3") (pintype "power_in"))
      (node (ref "U2") (pin "5") (pinfunction "GND_5") (pintype "power_in"))
      (node (ref "Y1") (pin "2") (pinfunction "GND_2") (pintype "passive"))
      (node (ref "Y1") (pin "4") (pinfunction "GND_4") (pintype "passive"))
      (node (ref "Y2") (pin "2") (pinfunction "GND_2") (pintype "passive"))
      (node (ref "Y2") (pin "4") (pinfunction "GND_4") (pintype "passive"))
    )
    (net (code "35") (name "Net-(LED1-Pad2)") (class "Default")
      (node (ref "LED1") (pin "2") (pinfunction "2_2") (pintype "passive"))
      (node (ref "R2") (pin "2") (pinfunction "2_2") (pintype "passive"))
    )
    (net (code "36") (name "Net-(LED2-Pad2)") (class "Default")
      (node (ref "LED2") (pin "2") (pinfunction "2_2") (pintype "passive"))
      (node (ref "R3") (pin "1") (pinfunction "1_1") (pintype "passive"))
    )
    (net (code "37") (name "Net-(LED3-Pad2)") (class "Default")
      (node (ref "LED3") (pin "2") (pinfunction "2_2") (pintype "passive"))
      (node (ref "R6") (pin "2") (pinfunction "2_2") (pintype "passive"))
    )
    (net (code "38") (name "Net-(LED4-Pad2)") (class "Default")
      (node (ref "LED4") (pin "2") (pinfunction "2_2") (pintype "passive"))
      (node (ref "R10") (pin "2") (pinfunction "2_2") (pintype "passive"))
    )
    (net (code "39") (name "Net-(LED5-Pad2)") (class "Default")
      (node (ref "LED5") (pin "2") (pinfunction "2_2") (pintype "passive"))
      (node (ref "R9") (pin "2") (pinfunction "2_2") (pintype "passive"))
    )
    (net (code "40") (name "Net-(LED6-Pad2)") (class "Default")
      (node (ref "LED6") (pin "2") (pinfunction "2_2") (pintype "passive"))
      (node (ref "R11") (pin "2") (pinfunction "2_2") (pintype "passive"))
    )
    (net (code "41") (name "Net-(LED7-Pad2)") (class "Default")
      (node (ref "LED7") (pin "2") (pinfunction "2_2") (pintype "passive"))
      (node (ref "R12") (pin "2") (pinfunction "2_2") (pintype "passive"))
    )
    (net (code "42") (name "Net-(PS1-IN)") (class "Default")
      (node (ref "C10") (pin "2") (pinfunction "2_2") (pintype "passive"))
      (node (ref "PS1") (pin "3") (pinfunction "IN_3") (pintype "power_in"))
      (node (ref "SW3") (pin "2") (pinfunction "2_2") (pintype "passive"))
    )
    (net (code "43") (name "Net-(TP5-Sgn)") (class "Default")
      (node (ref "R5") (pin "2") (pinfunction "2_2") (pintype "passive"))
      (node (ref "SW3") (pin "1") (pinfunction "1_1") (pintype "passive"))
      (node (ref "TP5") (pin "1") (pinfunction "Sgn_1") (pintype "passive"))
    )
    (net (code "44") (name "Net-(U1-RXD)") (class "Default")
      (node (ref "R13") (pin "2") (pinfunction "2_2") (pintype "passive"))
      (node (ref "U1") (pin "3") (pinfunction "RXD_3") (pintype "passive"))
    )
    (net (code "45") (name "Net-(U1-TXD)") (class "Default")
      (node (ref "R7") (pin "2") (pinfunction "2_2") (pintype "passive"))
      (node (ref "U1") (pin "2") (pinfunction "TXD_2") (pintype "passive"))
    )
    (net (code "46") (name "Net-(U1-V3)") (class "Default")
      (node (ref "C6") (pin "2") (pinfunction "2_2") (pintype "passive"))
      (node (ref "U1") (pin "4") (pinfunction "V3_4") (pintype "passive"))
    )
    (net (code "47") (name "VUSB_5V") (class "Default")
      (node (ref "C3") (pin "2") (pinfunction "2_2") (pintype "passive"))
      (node (ref "J1") (pin "1") (pinfunction "VBUS_1") (pintype "passive"))
      (node (ref "LED2") (pin "1") (pinfunction "1_1") (pintype "passive"))
      (node (ref "SW2") (pin "3") (pinfunction "3_3") (pintype "passive"))
    )
    (net (code "48") (name "unconnected-(D1-IO-3-Pad4)") (class "Default")
      (node (ref "D1") (pin "4") (pinfunction "IO-3_4") (pintype "passive"))
    )
    (net (code "49") (name "unconnected-(D1-IO-4-Pad6)") (class "Default")
      (node (ref "D1") (pin "6") (pinfunction "IO-4_6") (pintype "passive"))
    )
    (net (code "50") (name "unconnected-(J1-ID-Pad4)") (class "Default")
      (node (ref "J1") (pin "4") (pinfunction "ID_4") (pintype "passive"))
    )
    (net (code "51") (name "unconnected-(J5-Pad8)") (class "Default")
      (node (ref "J5") (pin "8") (pinfunction "8_8") (pintype "passive"))
    )
    (net (code "52") (name "unconnected-(U1-CTS#-Pad9)") (class "Default")
      (node (ref "U1") (pin "9") (pinfunction "CTS#_9") (pintype "passive"))
    )
    (net (code "53") (name "unconnected-(U1-DCD#-Pad12)") (class "Default")
      (node (ref "U1") (pin "12") (pinfunction "DCD#_12") (pintype "passive"))
    )
    (net (code "54") (name "unconnected-(U1-DSR#-Pad10)") (class "Default")
      (node (ref "U1") (pin "10") (pinfunction "DSR#_10") (pintype "passive"))
    )
    (net (code "55") (name "unconnected-(U1-RI#-Pad11)") (class "Default")
      (node (ref "U1") (pin "11") (pinfunction "RI#_11") (pintype "passive"))
    )
    (net (code "56") (name "unconnected-(U1-RS232-Pad15)") (class "Default")
      (node (ref "U1") (pin "15") (pinfunction "RS232_15") (pintype "passive"))
    )
    (net (code "57") (name "unconnected-(U1-RTS#-Pad14)") (class "Default")
      (node (ref "U1") (pin "14") (pinfunction "RTS#_14") (pintype "passive"))
    )
    (net (code "58") (name "unconnected-(U2-ADC6-Pad19)") (class "Default")
      (node (ref "U2") (pin "19") (pinfunction "ADC6_19") (pintype "bidirectional"))
    )
    (net (code "59") (name "unconnected-(U2-ADC7-Pad22)") (class "Default")
      (node (ref "U2") (pin "22") (pinfunction "ADC7_22") (pintype "bidirectional"))
    )
  )
)
